# 05_SSRs.net
KiCad netlist of a schematic drawn in Altium Designer
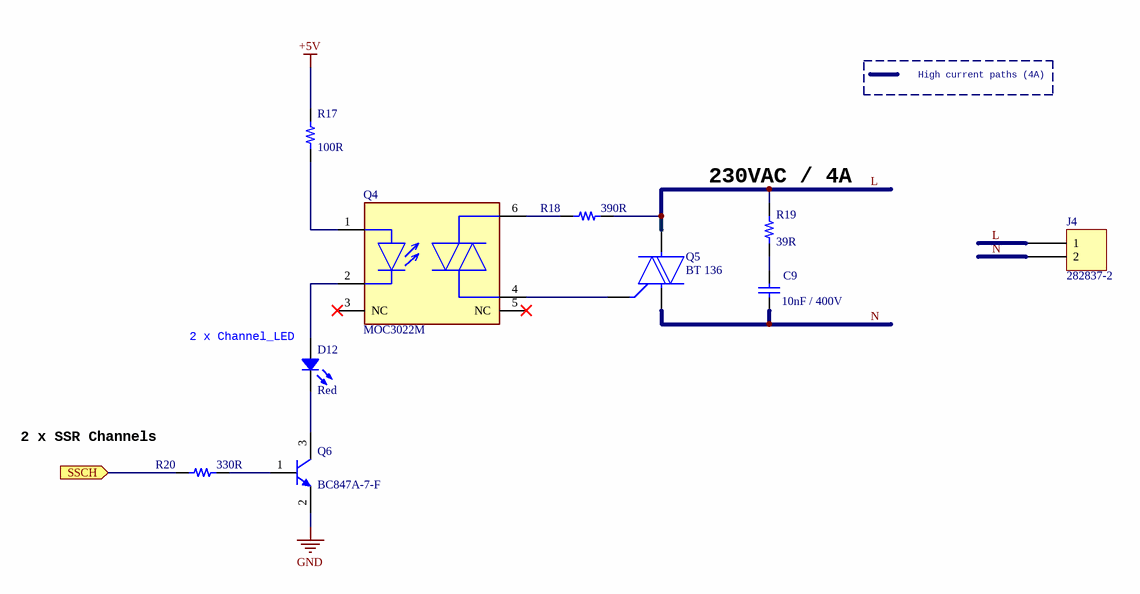
[diagram p0: 05.SSRs.SchDoc]

(export (version "E")
  (design (tool "Eeschema 10.0.6"))
  (components
    (comp (ref "C9")
      (value "10nF / 400V")
      (footprint "CAPRR1000W60L1200T500H830")
      (description "10nF ±5% 400V Plugin,P=10mm Polypropylene Film Capacitors (CBB) ROHS")
      (fields
        (field (name "MANUFACTURER PART NUMBER") "CFC2G103JE1J12075100")
        (field (name "MANUFACTURER") "Dersonic")
      )
      (libsource (lib "Smart_Wifi_Control_System_Rev_A.1.0") (part "Cap"))
    )
    (comp (ref "D12")
      (value "Red")
      (footprint "LED 0603_1608 RED")
      (description "-40℃~+85℃ Red 0603 Light Emitting Diodes (LED) ROHS")
      (fields
        (field (name "MANUFACTURER PART NUMBER") "KT-0603R")
        (field (name "MANUFACTURER") "Hubei KENTO Elec")
      )
      (libsource (lib "Celestial Altium Library - altium_library") (part "LED"))
    )
    (comp (ref "J4")
      (value "282837-2")
      (footprint "TE 282837-2")
      (description "TERM BLK 2P SIDE ENT 5.08MM PCB")
      (fields
        (field (name "MANUFACTURER") "TE Connectivity AMP Connectors")
        (field (name "JLC PART NUMBER") "C592976")
      )
      (libsource (lib "Celestial Altium Library - altium_library") (part "2 Pin"))
    )
    (comp (ref "Q4")
      (value "MOC3022M")
      (footprint "FP-646BY-MFG")
      (description "60mA 400V 1.15V Two-way thyristor DIP-6 Optocouplers - Thyristor Signal Output ROHS")
      (fields
        (field (name "MANUFACTURER") "UMW(Youtai Semiconductor Co., Ltd.)")
        (field (name "JLC PART NUMBER") "C2842958")
      )
      (libsource (lib "Altium Content Vault") (part "ac99fbad1a7223516b687fb475d83a7"))
    )
    (comp (ref "Q5")
      (value "BT 136")
      (footprint "FP-TO-220AB_Ins-MFG")
      (description "1W 4A 27A 1个双向可控硅 TO-220 TRIACs ROHS")
      (fields (field (name "MANUFACTURER") "KY") (field (name "MANUFACTURER PART NUMBER") "BT136-800E"))
      (libsource (lib "Altium Content Vault") (part "f4fece21ac4a8209e2c36b39bc58009"))
    )
    (comp (ref "Q6")
      (value "BC847A-7-F")
      (footprint "DIODES SOT-23-3")
      (description "65V 310mW 180@2mA,5V 100mA NPN SOT-23 Bipolar Transistors - BJT ROHS")
      (fields (field (name "MANUFACTURER") "Diodes Incorporated") (field (name "JLC PART NUMBER") "C2760576"))
      (libsource (lib "Celestial Altium Library - altium_library") (part "DIODES INC NPN SOT-23-3"))
    )
    (comp (ref "R17")
      (value "100R")
      (footprint "RES 0603_1608")
      (description "100mW Thick Film Resistors ±5% ±200ppm/℃ 100Ω 0603 Chip Resistor - Surface Mount ROHS")
      (fields
        (field (name "MANUFACTURER PART NUMBER") "TR0603D100RP0550Z")
        (field (name "MANUFACTURER") "Ever Ohms Tech")
      )
      (libsource (lib "Celestial Altium Library - altium_library") (part "Resistor"))
    )
    (comp (ref "R18")
      (value "390R")
      (footprint "RES 1206_3216")
      (description "250mW Thick Film Resistors ±100ppm/℃ ±5% 390Ω 1206 Chip Resistor - Surface Mount ROHS")
      (fields
        (field (name "MANUFACTURER PART NUMBER") "1206W4J0391T5E")
        (field (name "MANUFACTURER") "UNI-ROYAL(Uniroyal Elec)")
      )
      (libsource (lib "Celestial Altium Library - altium_library") (part "Resistor"))
    )
    (comp (ref "R19")
      (value "39R")
      (footprint "RES 1210_3225")
      (description "750mW Thick Film Resistors ±5% ±200ppm/℃ 39Ω 1210 Chip Resistor - Surface Mount ROHS")
      (fields
        (field (name "MANUFACTURER PART NUMBER") "CR1210J30390G")
        (field (name "MANUFACTURER") "LIZ Elec")
      )
      (libsource (lib "Celestial Altium Library - altium_library") (part "Resistor"))
    )
    (comp (ref "R20")
      (value "330R")
      (footprint "RES 0603_1608")
      (description "100mW Thick Film Resistors ±100ppm/℃ ±1% 330Ω 0603 Chip Resistor - Surface Mount ROHS")
      (fields
        (field (name "MANUFACTURER PART NUMBER") "0603WAF3300T5E")
        (field (name "MANUFACTURER") "UNI-ROYAL(Uniroyal Elec)")
      )
      (libsource (lib "Celestial Altium Library - altium_library") (part "Resistor"))
    )
  )
  (nets
    (net (code "1") (name "+5V") (class "Default")
      (node (ref "R17") (pin "2") (pinfunction "2_2") (pintype "passive"))
    )
    (net (code "2") (name "/L") (class "Default")
      (node (ref "J4") (pin "1") (pinfunction "1_1") (pintype "passive"))
      (node (ref "Q5") (pin "2") (pinfunction "A2_2") (pintype "passive"))
      (node (ref "R18") (pin "2") (pinfunction "2_2") (pintype "passive"))
      (node (ref "R19") (pin "2") (pinfunction "2_2") (pintype "passive"))
    )
    (net (code "3") (name "/N") (class "Default")
      (node (ref "C9") (pin "2") (pinfunction "2_2") (pintype "passive"))
      (node (ref "J4") (pin "2") (pinfunction "2_2") (pintype "passive"))
      (node (ref "Q5") (pin "1") (pinfunction "A1_1") (pintype "passive"))
    )
    (net (code "4") (name "/SSCH") (class "Default")
      (node (ref "R20") (pin "1") (pinfunction "1_1") (pintype "passive"))
    )
    (net (code "5") (name "GND") (class "Default")
      (node (ref "Q6") (pin "2") (pinfunction "E_2") (pintype "passive"))
    )
    (net (code "6") (name "Net-(C9-Pad1)") (class "Default")
      (node (ref "C9") (pin "1") (pinfunction "1_1") (pintype "passive"))
      (node (ref "R19") (pin "1") (pinfunction "1_1") (pintype "passive"))
    )
    (net (code "7") (name "Net-(Q4-1_MAIN_TERM.)") (class "Default")
      (node (ref "Q4") (pin "4") (pinfunction "1_MAIN_TERM._4") (pintype "passive"))
      (node (ref "Q5") (pin "3") (pinfunction "G_3") (pintype "passive"))
    )
    (net (code "8") (name "Net-(Q4-2_MAIN_TERM.)") (class "Default")
      (node (ref "Q4") (pin "6") (pinfunction "2_MAIN_TERM._6") (pintype "passive"))
      (node (ref "R18") (pin "1") (pinfunction "1_1") (pintype "passive"))
    )
    (net (code "9") (name "Net-(Q4-A)") (class "Default")
      (node (ref "Q4") (pin "1") (pinfunction "A_1") (pintype "passive"))
      (node (ref "R17") (pin "1") (pinfunction "1_1") (pintype "passive"))
    )
    (net (code "10") (name "Net-(Q4-C)") (class "Default")
      (node (ref "D12") (pin "1") (pinfunction "1_1") (pintype "passive"))
      (node (ref "Q4") (pin "2") (pinfunction "C_2") (pintype "passive"))
    )
    (net (code "11") (name "Net-(Q6-B)") (class "Default")
      (node (ref "Q6") (pin "1") (pinfunction "B_1") (pintype "passive"))
      (node (ref "R20") (pin "2") (pinfunction "2_2") (pintype "passive"))
    )
    (net (code "12") (name "Net-(Q6-C)") (class "Default")
      (node (ref "D12") (pin "2") (pinfunction "2_2") (pintype "passive"))
      (node (ref "Q6") (pin "3") (pinfunction "C_3") (pintype "passive"))
    )
    (net (code "13") (name "unconnected-(Q4-NC-Pad3)") (class "Default")
      (node (ref "Q4") (pin "3") (pinfunction "NC_3") (pintype "passive+no_connect"))
    )
    (net (code "14") (name "unconnected-(Q4-NC-Pad5)") (class "Default")
      (node (ref "Q4") (pin "5") (pinfunction "NC_5") (pintype "passive+no_connect"))
    )
  )
)
